# SDCard.net
KiCad netlist of a schematic drawn in Altium Designer
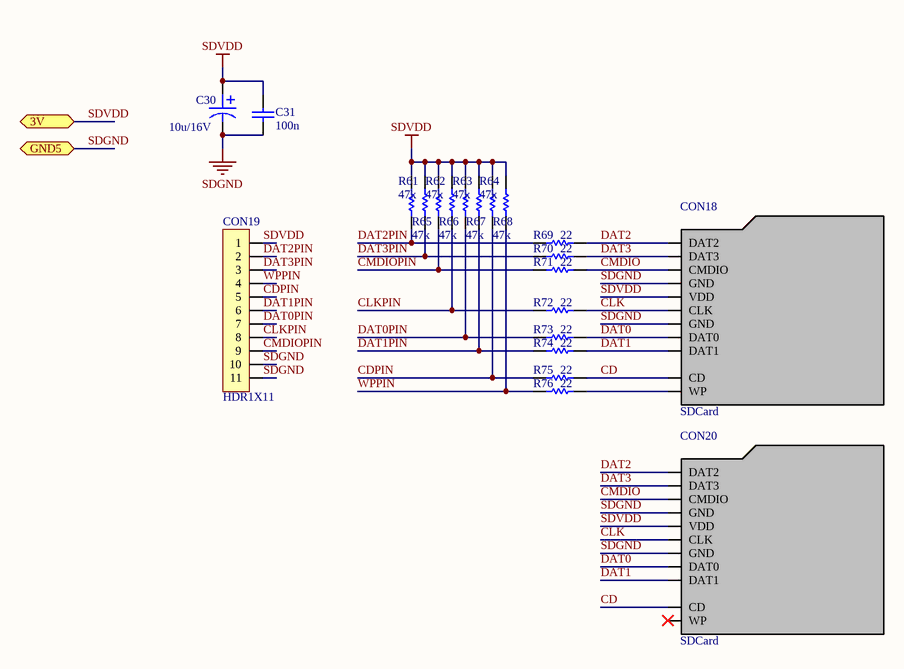
[diagram p0: SDCard.SchDoc]

(export (version "E")
  (design (tool "Eeschema 10.0.6"))
  (components
    (comp (ref "C30")
      (value "10u/16V")
      (footprint "dimploma:CA")
      (libsource (lib "diploma") (part "ELECTROLYTIC_CAPACITOR"))
    )
    (comp (ref "C31")
      (value "100n")
      (footprint "dimploma:0805C")
      (libsource (lib "diploma") (part "CAPACITOR"))
    )
    (comp (ref "CON18")
      (value "SDCard")
      (footprint "dimploma:SDCard")
      (libsource (lib "diploma") (part "SDCard"))
    )
    (comp (ref "CON19")
      (value "HDR1X11")
      (footprint "dimploma:HDR1X11RAST")
      (libsource (lib "diploma") (part "HDR1X11"))
    )
    (comp (ref "CON20")
      (value "SDCard")
      (footprint "dimploma:MICROSDCARD")
      (libsource (lib "diploma") (part "SDCard"))
    )
    (comp (ref "R61")
      (value "47k")
      (footprint "dimploma:0805R")
      (libsource (lib "diploma") (part "RESISTOR"))
    )
    (comp (ref "R62")
      (value "47k")
      (footprint "dimploma:0805R")
      (libsource (lib "diploma") (part "RESISTOR"))
    )
    (comp (ref "R63")
      (value "47k")
      (footprint "dimploma:0805R")
      (libsource (lib "diploma") (part "RESISTOR"))
    )
    (comp (ref "R64")
      (value "47k")
      (footprint "dimploma:0805R")
      (libsource (lib "diploma") (part "RESISTOR"))
    )
    (comp (ref "R65")
      (value "47k")
      (footprint "dimploma:0805R")
      (libsource (lib "diploma") (part "RESISTOR"))
    )
    (comp (ref "R66")
      (value "47k")
      (footprint "dimploma:0805R")
      (libsource (lib "diploma") (part "RESISTOR"))
    )
    (comp (ref "R67")
      (value "47k")
      (footprint "dimploma:0805R")
      (libsource (lib "diploma") (part "RESISTOR"))
    )
    (comp (ref "R68")
      (value "47k")
      (footprint "dimploma:0805R")
      (libsource (lib "diploma") (part "RESISTOR"))
    )
    (comp (ref "R69") (value "22") (footprint "dimploma:0805R") (libsource (lib "diploma") (part "RESISTOR")))
    (comp (ref "R70") (value "22") (footprint "dimploma:0805R") (libsource (lib "diploma") (part "RESISTOR")))
    (comp (ref "R71") (value "22") (footprint "dimploma:0805R") (libsource (lib "diploma") (part "RESISTOR")))
    (comp (ref "R72") (value "22") (footprint "dimploma:0805R") (libsource (lib "diploma") (part "RESISTOR")))
    (comp (ref "R73") (value "22") (footprint "dimploma:0805R") (libsource (lib "diploma") (part "RESISTOR")))
    (comp (ref "R74") (value "22") (footprint "dimploma:0805R") (libsource (lib "diploma") (part "RESISTOR")))
    (comp (ref "R75") (value "22") (footprint "dimploma:0805R") (libsource (lib "diploma") (part "RESISTOR")))
    (comp (ref "R76") (value "22") (footprint "dimploma:0805R") (libsource (lib "diploma") (part "RESISTOR")))
  )
  (nets
    (net (code "1") (name "/CD") (class "Default")
      (node (ref "CON18") (pin "CD") (pinfunction "CD_CD") (pintype "passive"))
      (node (ref "CON20") (pin "CD") (pinfunction "CD_CD") (pintype "passive"))
      (node (ref "R75") (pin "2") (pinfunction "2_2") (pintype "passive"))
    )
    (net (code "2") (name "/CDPIN") (class "Default")
      (node (ref "CON19") (pin "5") (pinfunction "5_5") (pintype "passive"))
      (node (ref "R64") (pin "1") (pinfunction "1_1") (pintype "passive"))
      (node (ref "R75") (pin "1") (pinfunction "1_1") (pintype "passive"))
    )
    (net (code "3") (name "/CLK") (class "Default")
      (node (ref "CON18") (pin "CLK") (pinfunction "CLK_CLK") (pintype "passive"))
      (node (ref "CON20") (pin "CLK") (pinfunction "CLK_CLK") (pintype "passive"))
      (node (ref "R72") (pin "2") (pinfunction "2_2") (pintype "passive"))
    )
    (net (code "4") (name "/CLKPIN") (class "Default")
      (node (ref "CON19") (pin "8") (pinfunction "8_8") (pintype "passive"))
      (node (ref "R66") (pin "1") (pinfunction "1_1") (pintype "passive"))
      (node (ref "R72") (pin "1") (pinfunction "1_1") (pintype "passive"))
    )
    (net (code "5") (name "/CMDIO") (class "Default")
      (node (ref "CON18") (pin "CMDIO") (pinfunction "CMDIO_CMDIO") (pintype "passive"))
      (node (ref "CON20") (pin "CMDIO") (pinfunction "CMDIO_CMDIO") (pintype "passive"))
      (node (ref "R71") (pin "2") (pinfunction "2_2") (pintype "passive"))
    )
    (net (code "6") (name "/CMDIOPIN") (class "Default")
      (node (ref "CON19") (pin "9") (pinfunction "9_9") (pintype "passive"))
      (node (ref "R62") (pin "1") (pinfunction "1_1") (pintype "passive"))
      (node (ref "R71") (pin "1") (pinfunction "1_1") (pintype "passive"))
    )
    (net (code "7") (name "/DAT0") (class "Default")
      (node (ref "CON18") (pin "DAT0") (pinfunction "DAT0_DAT0") (pintype "passive"))
      (node (ref "CON20") (pin "DAT0") (pinfunction "DAT0_DAT0") (pintype "passive"))
      (node (ref "R73") (pin "2") (pinfunction "2_2") (pintype "passive"))
    )
    (net (code "8") (name "/DAT0PIN") (class "Default")
      (node (ref "CON19") (pin "7") (pinfunction "7_7") (pintype "passive"))
      (node (ref "R63") (pin "1") (pinfunction "1_1") (pintype "passive"))
      (node (ref "R73") (pin "1") (pinfunction "1_1") (pintype "passive"))
    )
    (net (code "9") (name "/DAT1") (class "Default")
      (node (ref "CON18") (pin "DAT1") (pinfunction "DAT1_DAT1") (pintype "passive"))
      (node (ref "CON20") (pin "DAT1") (pinfunction "DAT1_DAT1") (pintype "passive"))
      (node (ref "R74") (pin "2") (pinfunction "2_2") (pintype "passive"))
    )
    (net (code "10") (name "/DAT1PIN") (class "Default")
      (node (ref "CON19") (pin "6") (pinfunction "6_6") (pintype "passive"))
      (node (ref "R67") (pin "1") (pinfunction "1_1") (pintype "passive"))
      (node (ref "R74") (pin "1") (pinfunction "1_1") (pintype "passive"))
    )
    (net (code "11") (name "/DAT2") (class "Default")
      (node (ref "CON18") (pin "DAT2") (pinfunction "DAT2_DAT2") (pintype "passive"))
      (node (ref "CON20") (pin "DAT2") (pinfunction "DAT2_DAT2") (pintype "passive"))
      (node (ref "R69") (pin "2") (pinfunction "2_2") (pintype "passive"))
    )
    (net (code "12") (name "/DAT2PIN") (class "Default")
      (node (ref "CON19") (pin "2") (pinfunction "2_2") (pintype "passive"))
      (node (ref "R61") (pin "1") (pinfunction "1_1") (pintype "passive"))
      (node (ref "R69") (pin "1") (pinfunction "1_1") (pintype "passive"))
    )
    (net (code "13") (name "/DAT3") (class "Default")
      (node (ref "CON18") (pin "DAT3") (pinfunction "DAT3_DAT3") (pintype "passive"))
      (node (ref "CON20") (pin "DAT3") (pinfunction "DAT3_DAT3") (pintype "passive"))
      (node (ref "R70") (pin "2") (pinfunction "2_2") (pintype "passive"))
    )
    (net (code "14") (name "/DAT3PIN") (class "Default")
      (node (ref "CON19") (pin "3") (pinfunction "3_3") (pintype "passive"))
      (node (ref "R65") (pin "1") (pinfunction "1_1") (pintype "passive"))
      (node (ref "R70") (pin "1") (pinfunction "1_1") (pintype "passive"))
    )
    (net (code "15") (name "/WPPIN") (class "Default")
      (node (ref "CON19") (pin "4") (pinfunction "4_4") (pintype "passive"))
      (node (ref "R68") (pin "1") (pinfunction "1_1") (pintype "passive"))
      (node (ref "R76") (pin "1") (pinfunction "1_1") (pintype "passive"))
    )
    (net (code "16") (name "Net-(CON18-PadWP)") (class "Default")
      (node (ref "CON18") (pin "WP") (pinfunction "WP_WP") (pintype "passive"))
      (node (ref "R76") (pin "2") (pinfunction "2_2") (pintype "passive"))
    )
    (net (code "17") (name "SDGND") (class "Default")
      (node (ref "C30") (pin "2") (pinfunction "2_2") (pintype "passive"))
      (node (ref "C31") (pin "1") (pinfunction "1_1") (pintype "passive"))
      (node (ref "CON18") (pin "GND") (pinfunction "GND_GND") (pintype "passive"))
      (node (ref "CON19") (pin "10") (pinfunction "10_10") (pintype "passive"))
      (node (ref "CON19") (pin "11") (pinfunction "11_11") (pintype "passive"))
      (node (ref "CON20") (pin "GND") (pinfunction "GND_GND") (pintype "passive"))
    )
    (net (code "18") (name "SDVDD") (class "Default")
      (node (ref "C30") (pin "1") (pinfunction "1_1") (pintype "passive"))
      (node (ref "C31") (pin "2") (pinfunction "2_2") (pintype "passive"))
      (node (ref "CON18") (pin "VDD") (pinfunction "VDD_VDD") (pintype "passive"))
      (node (ref "CON19") (pin "1") (pinfunction "1_1") (pintype "passive"))
      (node (ref "CON20") (pin "VDD") (pinfunction "VDD_VDD") (pintype "passive"))
      (node (ref "R61") (pin "2") (pinfunction "2_2") (pintype "passive"))
      (node (ref "R62") (pin "2") (pinfunction "2_2") (pintype "passive"))
      (node (ref "R63") (pin "2") (pinfunction "2_2") (pintype "passive"))
      (node (ref "R64") (pin "2") (pinfunction "2_2") (pintype "passive"))
      (node (ref "R65") (pin "2") (pinfunction "2_2") (pintype "passive"))
      (node (ref "R66") (pin "2") (pinfunction "2_2") (pintype "passive"))
      (node (ref "R67") (pin "2") (pinfunction "2_2") (pintype "passive"))
      (node (ref "R68") (pin "2") (pinfunction "2_2") (pintype "passive"))
    )
    (net (code "19") (name "unconnected-(CON20-PadWP)") (class "Default")
      (node (ref "CON20") (pin "WP") (pinfunction "WP_WP") (pintype "passive+no_connect"))
    )
  )
)
